# General_design.net
KiCad netlist of a schematic drawn in Altium Designer
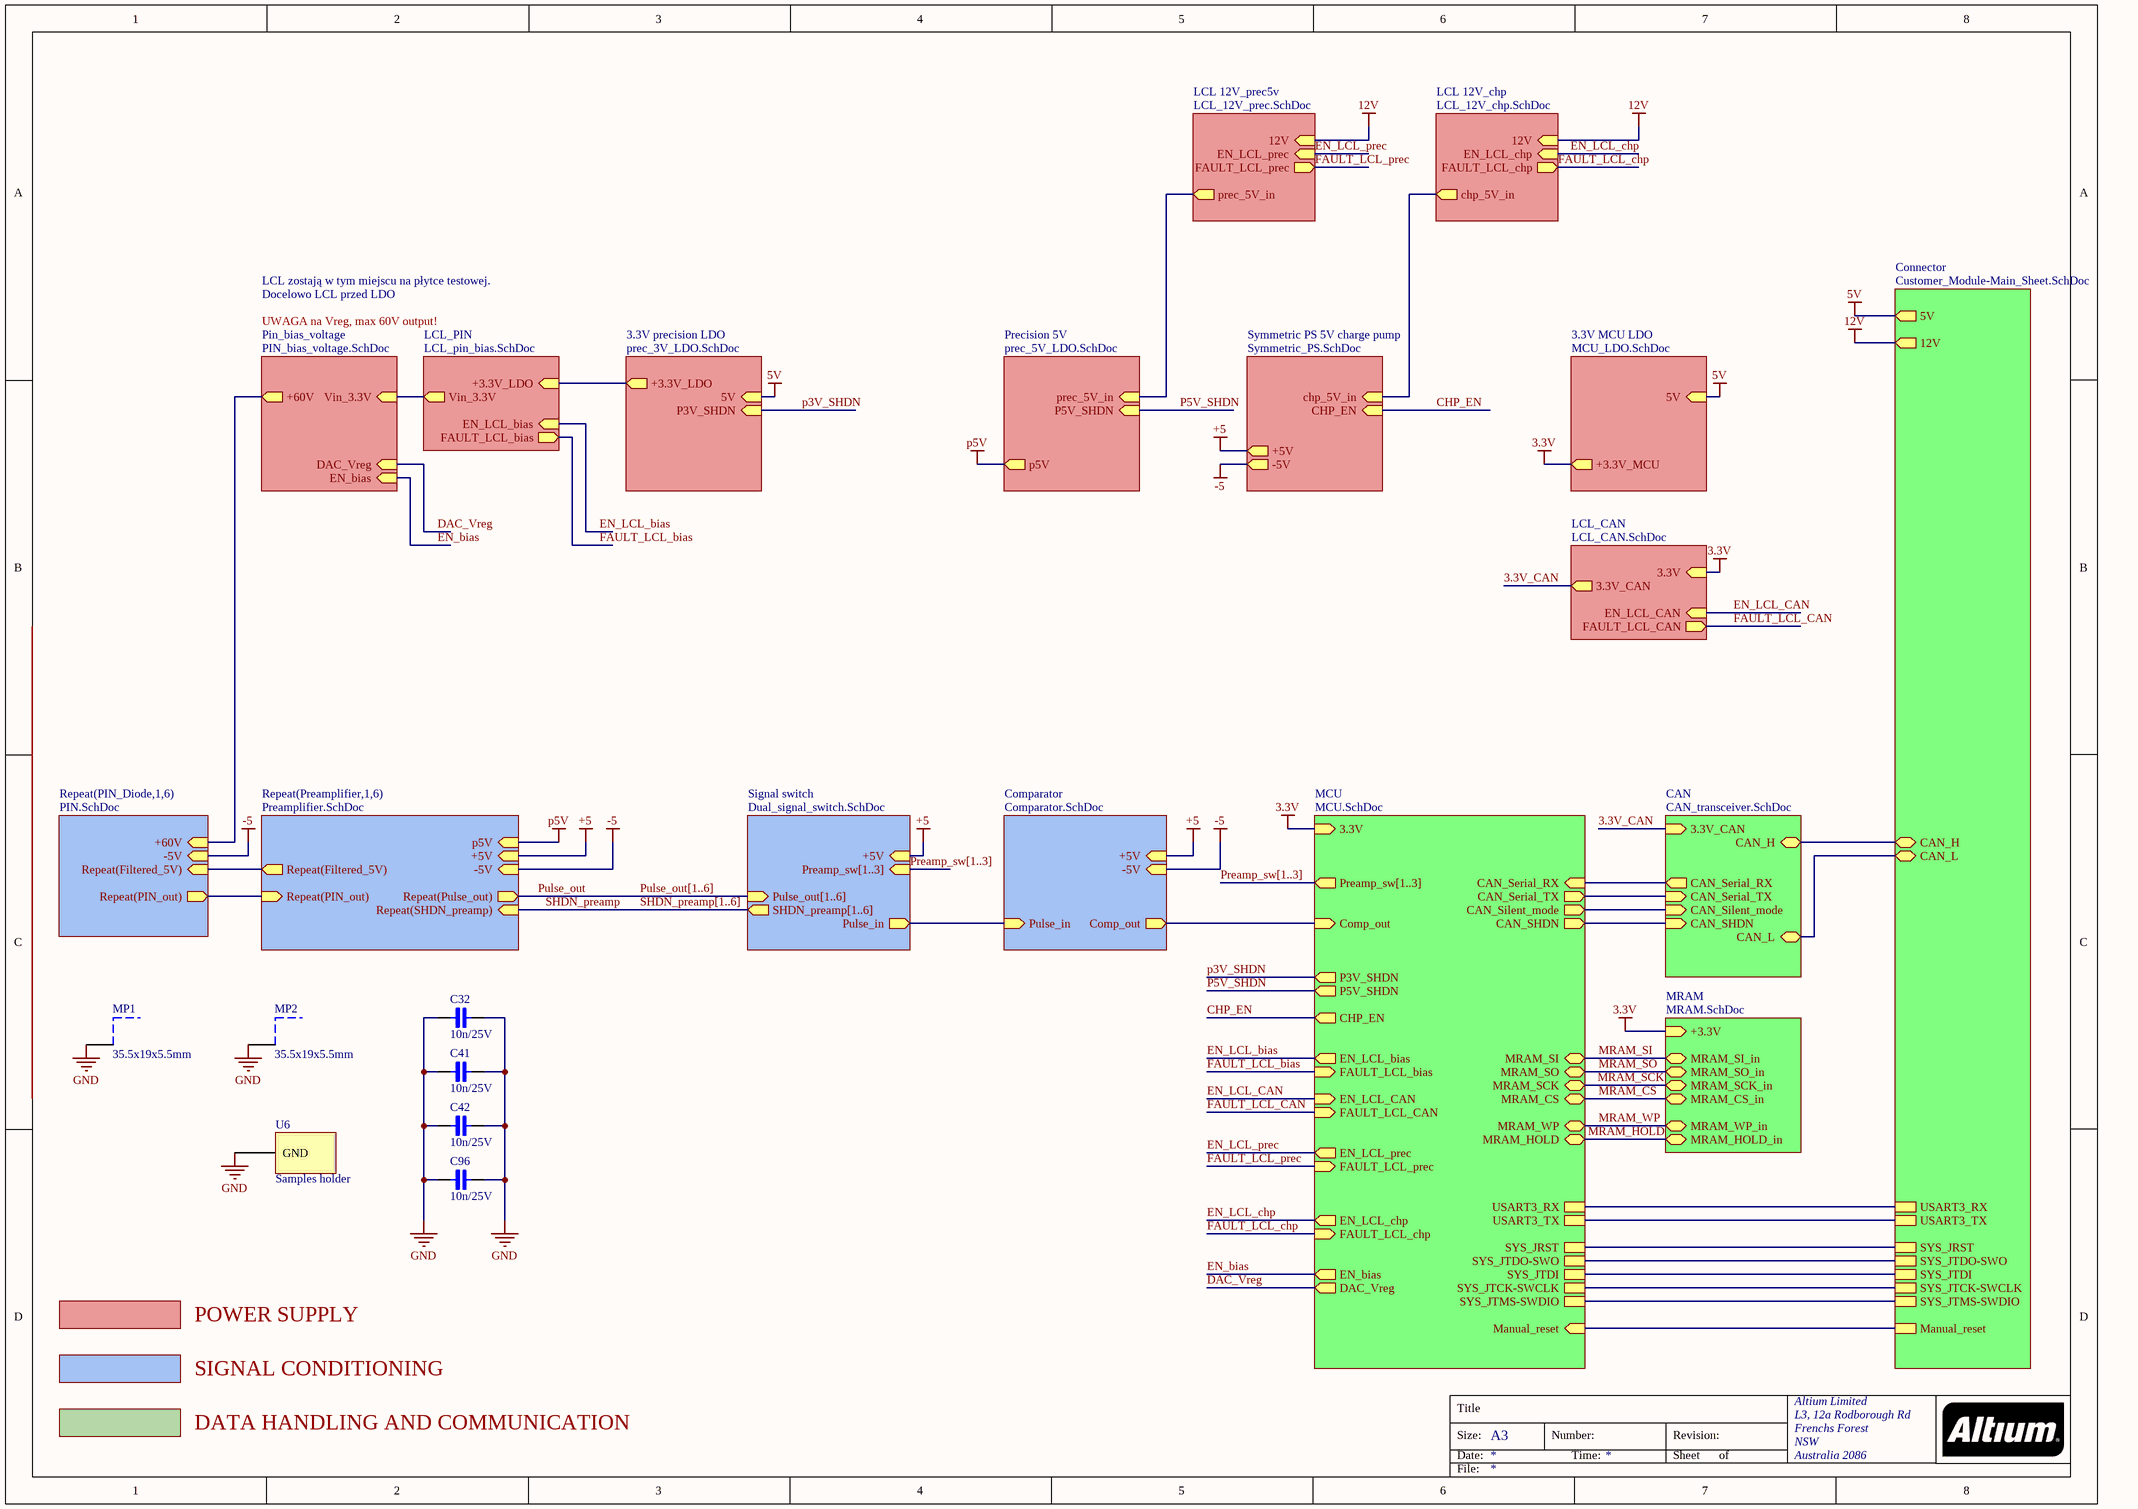
[diagram p0: General_design.SchDoc]

(export (version "E")
  (design (tool "Eeschema 10.0.6"))
  (components
    (comp (ref "C32")
      (value "10n/25V")
      (footprint "Cap_0402")
      (description "Ceramic Capacitor 10n / 0402 / 25V / ±5%, Wurth Elektronik MLCC")
      (libsource (lib "Cubesat_lib") (part "Cap_0402_10n"))
    )
    (comp (ref "C41")
      (value "10n/25V")
      (footprint "Cap_0402")
      (description "Ceramic Capacitor 10n / 0402 / 25V / ±5%, Wurth Elektronik MLCC")
      (libsource (lib "Cubesat_lib") (part "Cap_0402_10n"))
    )
    (comp (ref "C42")
      (value "10n/25V")
      (footprint "Cap_0402")
      (description "Ceramic Capacitor 10n / 0402 / 25V / ±5%, Wurth Elektronik MLCC")
      (libsource (lib "Cubesat_lib") (part "Cap_0402_10n"))
    )
    (comp (ref "C96")
      (value "10n/25V")
      (footprint "Cap_0402")
      (description "Ceramic Capacitor 10n / 0402 / 25V / ±5%, Wurth Elektronik MLCC")
      (libsource (lib "Cubesat_lib") (part "Cap_0402_10n"))
    )
    (comp (ref "MP1")
      (value "35.5x19x5.5mm")
      (footprint "Shiled_35x19")
      (description "WE-SHC Shielding Cabinet, SMT Frame Seamless, Tin Plated, Tray, 35.5x19x5.5mm")
      (fields
        (field (name "MANUFACTURER PART NUMBER") "3670355")
        (field (name "MANUFACTURER") "Wurth Elektronik")
      )
      (libsource (lib "Cubesat_lib") (part "Shield 35x19"))
    )
    (comp (ref "MP2")
      (value "35.5x19x5.5mm")
      (footprint "Shiled_35x19")
      (description "WE-SHC Shielding Cabinet, SMT Frame Seamless, Tin Plated, Tray, 35.5x19x5.5mm")
      (fields
        (field (name "MANUFACTURER PART NUMBER") "3670355")
        (field (name "MANUFACTURER") "Wurth Elektronik")
      )
      (libsource (lib "Cubesat_lib") (part "Shield 35x19"))
    )
    (comp (ref "U6")
      (value "Samples holder")
      (footprint "RAD_Samples_Holder")
      (description "Mechanical aprt")
      (libsource (lib "Cubesat_lib") (part "RAD_samples_holder"))
    )
  )
  (nets
    (net (code "55") (name "GND") (class "Default")
      (node (ref "C32") (pin "1") (pinfunction "1_1") (pintype "passive"))
      (node (ref "C32") (pin "2") (pinfunction "2_2") (pintype "passive"))
      (node (ref "C41") (pin "1") (pinfunction "1_1") (pintype "passive"))
      (node (ref "C41") (pin "2") (pinfunction "2_2") (pintype "passive"))
      (node (ref "C42") (pin "1") (pinfunction "1_1") (pintype "passive"))
      (node (ref "C42") (pin "2") (pinfunction "2_2") (pintype "passive"))
      (node (ref "C96") (pin "1") (pinfunction "1_1") (pintype "passive"))
      (node (ref "C96") (pin "2") (pinfunction "2_2") (pintype "passive"))
      (node (ref "MP1") (pin "1") (pinfunction "1_1") (pintype "passive"))
      (node (ref "MP2") (pin "1") (pinfunction "1_1") (pintype "passive"))
      (node (ref "U6") (pin "5") (pinfunction "GND_5") (pintype "passive"))
    )
  )
)
